# Copy_of_tsop_mux.net
KiCad netlist of a schematic drawn in Altium Designer
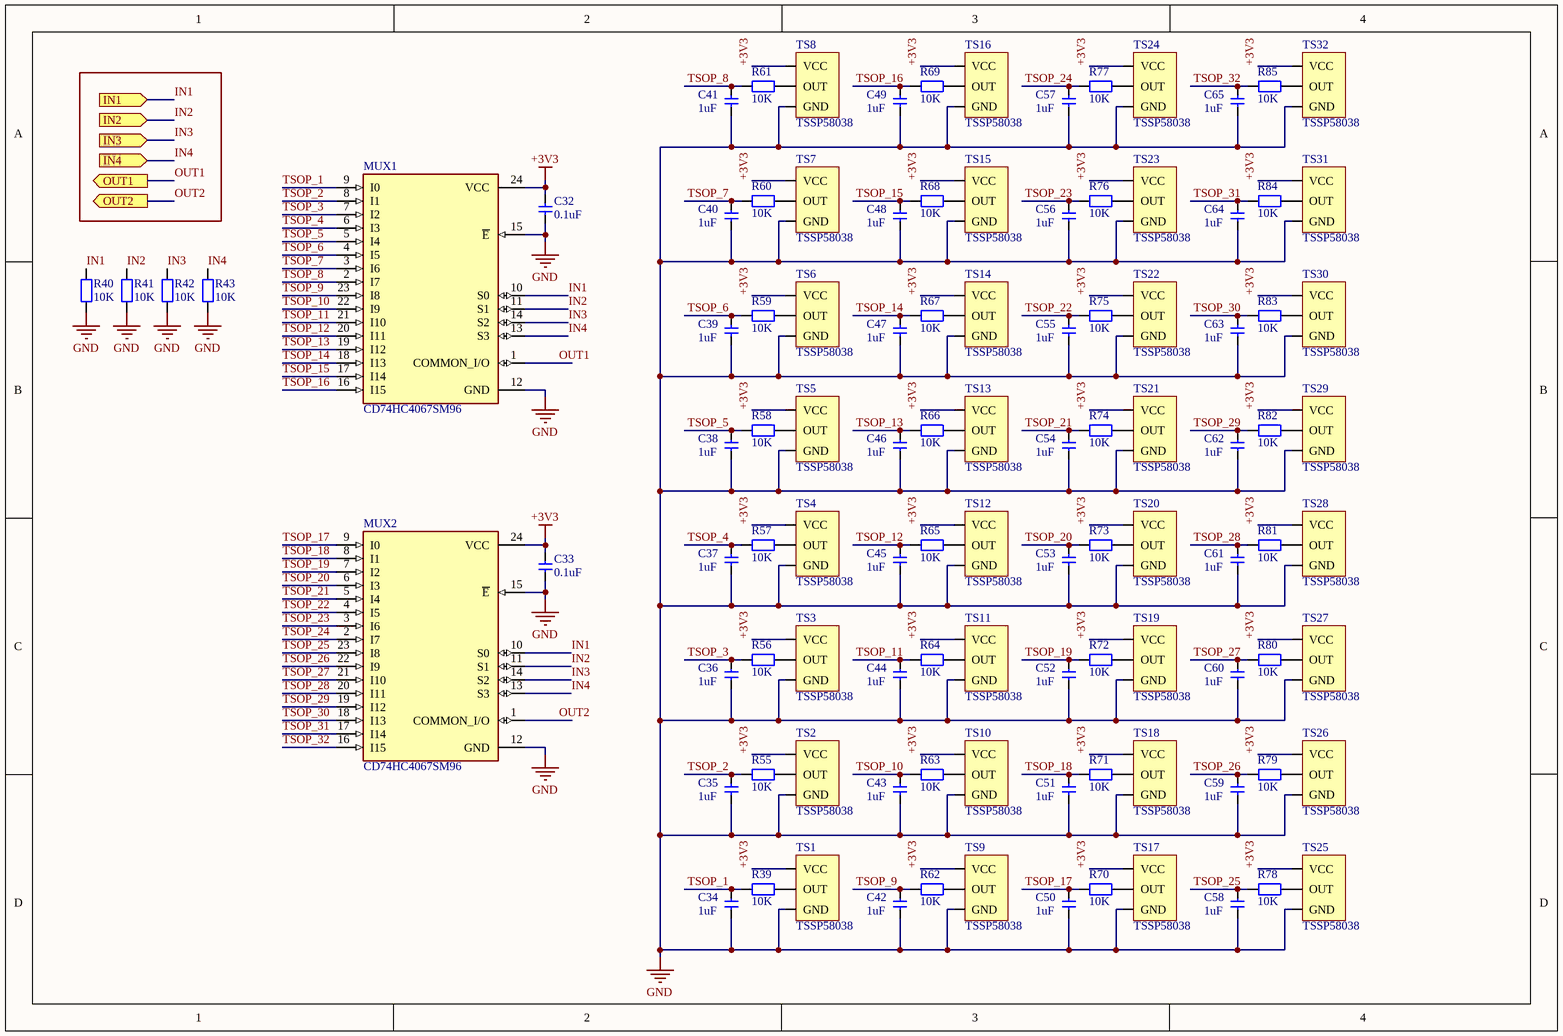
[diagram p0: Copy of tsop_mux.SchDoc]

(export (version "E")
  (design (tool "Eeschema 10.0.6"))
  (components
    (comp (ref "C32")
      (value "0.1uF")
      (footprint "CAP0805")
      (description "Ceramic SMD Cap")
      (libsource (lib "Asterisk") (part "CAP Ceramic"))
    )
    (comp (ref "C33")
      (value "0.1uF")
      (footprint "CAP0805")
      (description "Ceramic SMD Cap")
      (libsource (lib "Asterisk") (part "CAP Ceramic"))
    )
    (comp (ref "C34")
      (value "1uF")
      (footprint "CAP1206")
      (description "Ceramic SMD Cap")
      (libsource (lib "Asterisk") (part "CAP Ceramic"))
    )
    (comp (ref "C35")
      (value "1uF")
      (footprint "CAP1206")
      (description "Ceramic SMD Cap")
      (libsource (lib "Asterisk") (part "CAP Ceramic"))
    )
    (comp (ref "C36")
      (value "1uF")
      (footprint "CAP1206")
      (description "Ceramic SMD Cap")
      (libsource (lib "Asterisk") (part "CAP Ceramic"))
    )
    (comp (ref "C37")
      (value "1uF")
      (footprint "CAP1206")
      (description "Ceramic SMD Cap")
      (libsource (lib "Asterisk") (part "CAP Ceramic"))
    )
    (comp (ref "C38")
      (value "1uF")
      (footprint "CAP1206")
      (description "Ceramic SMD Cap")
      (libsource (lib "Asterisk") (part "CAP Ceramic"))
    )
    (comp (ref "C39")
      (value "1uF")
      (footprint "CAP1206")
      (description "Ceramic SMD Cap")
      (libsource (lib "Asterisk") (part "CAP Ceramic"))
    )
    (comp (ref "C40")
      (value "1uF")
      (footprint "CAP1206")
      (description "Ceramic SMD Cap")
      (libsource (lib "Asterisk") (part "CAP Ceramic"))
    )
    (comp (ref "C41")
      (value "1uF")
      (footprint "CAP1206")
      (description "Ceramic SMD Cap")
      (libsource (lib "Asterisk") (part "CAP Ceramic"))
    )
    (comp (ref "C42")
      (value "1uF")
      (footprint "CAP1206")
      (description "Ceramic SMD Cap")
      (libsource (lib "Asterisk") (part "CAP Ceramic"))
    )
    (comp (ref "C43")
      (value "1uF")
      (footprint "CAP1206")
      (description "Ceramic SMD Cap")
      (libsource (lib "Asterisk") (part "CAP Ceramic"))
    )
    (comp (ref "C44")
      (value "1uF")
      (footprint "CAP1206")
      (description "Ceramic SMD Cap")
      (libsource (lib "Asterisk") (part "CAP Ceramic"))
    )
    (comp (ref "C45")
      (value "1uF")
      (footprint "CAP1206")
      (description "Ceramic SMD Cap")
      (libsource (lib "Asterisk") (part "CAP Ceramic"))
    )
    (comp (ref "C46")
      (value "1uF")
      (footprint "CAP1206")
      (description "Ceramic SMD Cap")
      (libsource (lib "Asterisk") (part "CAP Ceramic"))
    )
    (comp (ref "C47")
      (value "1uF")
      (footprint "CAP1206")
      (description "Ceramic SMD Cap")
      (libsource (lib "Asterisk") (part "CAP Ceramic"))
    )
    (comp (ref "C48")
      (value "1uF")
      (footprint "CAP1206")
      (description "Ceramic SMD Cap")
      (libsource (lib "Asterisk") (part "CAP Ceramic"))
    )
    (comp (ref "C49")
      (value "1uF")
      (footprint "CAP1206")
      (description "Ceramic SMD Cap")
      (libsource (lib "Asterisk") (part "CAP Ceramic"))
    )
    (comp (ref "C50")
      (value "1uF")
      (footprint "CAP1206")
      (description "Ceramic SMD Cap")
      (libsource (lib "Asterisk") (part "CAP Ceramic"))
    )
    (comp (ref "C51")
      (value "1uF")
      (footprint "CAP1206")
      (description "Ceramic SMD Cap")
      (libsource (lib "Asterisk") (part "CAP Ceramic"))
    )
    (comp (ref "C52")
      (value "1uF")
      (footprint "CAP1206")
      (description "Ceramic SMD Cap")
      (libsource (lib "Asterisk") (part "CAP Ceramic"))
    )
    (comp (ref "C53")
      (value "1uF")
      (footprint "CAP1206")
      (description "Ceramic SMD Cap")
      (libsource (lib "Asterisk") (part "CAP Ceramic"))
    )
    (comp (ref "C54")
      (value "1uF")
      (footprint "CAP1206")
      (description "Ceramic SMD Cap")
      (libsource (lib "Asterisk") (part "CAP Ceramic"))
    )
    (comp (ref "C55")
      (value "1uF")
      (footprint "CAP1206")
      (description "Ceramic SMD Cap")
      (libsource (lib "Asterisk") (part "CAP Ceramic"))
    )
    (comp (ref "C56")
      (value "1uF")
      (footprint "CAP1206")
      (description "Ceramic SMD Cap")
      (libsource (lib "Asterisk") (part "CAP Ceramic"))
    )
    (comp (ref "C57")
      (value "1uF")
      (footprint "CAP1206")
      (description "Ceramic SMD Cap")
      (libsource (lib "Asterisk") (part "CAP Ceramic"))
    )
    (comp (ref "C58")
      (value "1uF")
      (footprint "CAP1206")
      (description "Ceramic SMD Cap")
      (libsource (lib "Asterisk") (part "CAP Ceramic"))
    )
    (comp (ref "C59")
      (value "1uF")
      (footprint "CAP1206")
      (description "Ceramic SMD Cap")
      (libsource (lib "Asterisk") (part "CAP Ceramic"))
    )
    (comp (ref "C60")
      (value "1uF")
      (footprint "CAP1206")
      (description "Ceramic SMD Cap")
      (libsource (lib "Asterisk") (part "CAP Ceramic"))
    )
    (comp (ref "C61")
      (value "1uF")
      (footprint "CAP1206")
      (description "Ceramic SMD Cap")
      (libsource (lib "Asterisk") (part "CAP Ceramic"))
    )
    (comp (ref "C62")
      (value "1uF")
      (footprint "CAP1206")
      (description "Ceramic SMD Cap")
      (libsource (lib "Asterisk") (part "CAP Ceramic"))
    )
    (comp (ref "C63")
      (value "1uF")
      (footprint "CAP1206")
      (description "Ceramic SMD Cap")
      (libsource (lib "Asterisk") (part "CAP Ceramic"))
    )
    (comp (ref "C64")
      (value "1uF")
      (footprint "CAP1206")
      (description "Ceramic SMD Cap")
      (libsource (lib "Asterisk") (part "CAP Ceramic"))
    )
    (comp (ref "C65")
      (value "1uF")
      (footprint "CAP1206")
      (description "Ceramic SMD Cap")
      (libsource (lib "Asterisk") (part "CAP Ceramic"))
    )
    (comp (ref "MUX1")
      (value "CD74HC4067SM96")
      (footprint "CD74HC4067SM96")
      (description "SSOP-24")
      (libsource (lib "Asterisk") (part "CD74HC4067SM96"))
    )
    (comp (ref "MUX2")
      (value "CD74HC4067SM96")
      (footprint "CD74HC4067SM96")
      (description "SSOP-24")
      (libsource (lib "Asterisk") (part "CD74HC4067SM96"))
    )
    (comp (ref "R39")
      (value "10K")
      (footprint "RES0603")
      (description "RES smd")
      (libsource (lib "Asterisk") (part "RES"))
    )
    (comp (ref "R40")
      (value "10K")
      (footprint "RES0805")
      (description "RES smd")
      (libsource (lib "Asterisk") (part "RES"))
    )
    (comp (ref "R41")
      (value "10K")
      (footprint "RES0805")
      (description "RES smd")
      (libsource (lib "Asterisk") (part "RES"))
    )
    (comp (ref "R42")
      (value "10K")
      (footprint "RES0805")
      (description "RES smd")
      (libsource (lib "Asterisk") (part "RES"))
    )
    (comp (ref "R43")
      (value "10K")
      (footprint "RES0805")
      (description "RES smd")
      (libsource (lib "Asterisk") (part "RES"))
    )
    (comp (ref "R55")
      (value "10K")
      (footprint "RES0603")
      (description "RES smd")
      (libsource (lib "Asterisk") (part "RES"))
    )
    (comp (ref "R56")
      (value "10K")
      (footprint "RES0603")
      (description "RES smd")
      (libsource (lib "Asterisk") (part "RES"))
    )
    (comp (ref "R57")
      (value "10K")
      (footprint "RES0603")
      (description "RES smd")
      (libsource (lib "Asterisk") (part "RES"))
    )
    (comp (ref "R58")
      (value "10K")
      (footprint "RES0603")
      (description "RES smd")
      (libsource (lib "Asterisk") (part "RES"))
    )
    (comp (ref "R59")
      (value "10K")
      (footprint "RES0603")
      (description "RES smd")
      (libsource (lib "Asterisk") (part "RES"))
    )
    (comp (ref "R60")
      (value "10K")
      (footprint "RES0603")
      (description "RES smd")
      (libsource (lib "Asterisk") (part "RES"))
    )
    (comp (ref "R61")
      (value "10K")
      (footprint "RES0603")
      (description "RES smd")
      (libsource (lib "Asterisk") (part "RES"))
    )
    (comp (ref "R62")
      (value "10K")
      (footprint "RES0603")
      (description "RES smd")
      (libsource (lib "Asterisk") (part "RES"))
    )
    (comp (ref "R63")
      (value "10K")
      (footprint "RES0603")
      (description "RES smd")
      (libsource (lib "Asterisk") (part "RES"))
    )
    (comp (ref "R64")
      (value "10K")
      (footprint "RES0603")
      (description "RES smd")
      (libsource (lib "Asterisk") (part "RES"))
    )
    (comp (ref "R65")
      (value "10K")
      (footprint "RES0603")
      (description "RES smd")
      (libsource (lib "Asterisk") (part "RES"))
    )
    (comp (ref "R66")
      (value "10K")
      (footprint "RES0603")
      (description "RES smd")
      (libsource (lib "Asterisk") (part "RES"))
    )
    (comp (ref "R67")
      (value "10K")
      (footprint "RES0603")
      (description "RES smd")
      (libsource (lib "Asterisk") (part "RES"))
    )
    (comp (ref "R68")
      (value "10K")
      (footprint "RES0603")
      (description "RES smd")
      (libsource (lib "Asterisk") (part "RES"))
    )
    (comp (ref "R69")
      (value "10K")
      (footprint "RES0603")
      (description "RES smd")
      (libsource (lib "Asterisk") (part "RES"))
    )
    (comp (ref "R70")
      (value "10K")
      (footprint "RES0603")
      (description "RES smd")
      (libsource (lib "Asterisk") (part "RES"))
    )
    (comp (ref "R71")
      (value "10K")
      (footprint "RES0603")
      (description "RES smd")
      (libsource (lib "Asterisk") (part "RES"))
    )
    (comp (ref "R72")
      (value "10K")
      (footprint "RES0603")
      (description "RES smd")
      (libsource (lib "Asterisk") (part "RES"))
    )
    (comp (ref "R73")
      (value "10K")
      (footprint "RES0603")
      (description "RES smd")
      (libsource (lib "Asterisk") (part "RES"))
    )
    (comp (ref "R74")
      (value "10K")
      (footprint "RES0603")
      (description "RES smd")
      (libsource (lib "Asterisk") (part "RES"))
    )
    (comp (ref "R75")
      (value "10K")
      (footprint "RES0603")
      (description "RES smd")
      (libsource (lib "Asterisk") (part "RES"))
    )
    (comp (ref "R76")
      (value "10K")
      (footprint "RES0603")
      (description "RES smd")
      (libsource (lib "Asterisk") (part "RES"))
    )
    (comp (ref "R77")
      (value "10K")
      (footprint "RES0603")
      (description "RES smd")
      (libsource (lib "Asterisk") (part "RES"))
    )
    (comp (ref "R78")
      (value "10K")
      (footprint "RES0603")
      (description "RES smd")
      (libsource (lib "Asterisk") (part "RES"))
    )
    (comp (ref "R79")
      (value "10K")
      (footprint "RES0603")
      (description "RES smd")
      (libsource (lib "Asterisk") (part "RES"))
    )
    (comp (ref "R80")
      (value "10K")
      (footprint "RES0603")
      (description "RES smd")
      (libsource (lib "Asterisk") (part "RES"))
    )
    (comp (ref "R81")
      (value "10K")
      (footprint "RES0603")
      (description "RES smd")
      (libsource (lib "Asterisk") (part "RES"))
    )
    (comp (ref "R82")
      (value "10K")
      (footprint "RES0603")
      (description "RES smd")
      (libsource (lib "Asterisk") (part "RES"))
    )
    (comp (ref "R83")
      (value "10K")
      (footprint "RES0603")
      (description "RES smd")
      (libsource (lib "Asterisk") (part "RES"))
    )
    (comp (ref "R84")
      (value "10K")
      (footprint "RES0603")
      (description "RES smd")
      (libsource (lib "Asterisk") (part "RES"))
    )
    (comp (ref "R85")
      (value "10K")
      (footprint "RES0603")
      (description "RES smd")
      (libsource (lib "Asterisk") (part "RES"))
    )
    (comp (ref "TS1")
      (value "TSSP58038")
      (footprint "TSSP58038")
      (libsource (lib "Asterisk") (part "TSSP58038"))
    )
    (comp (ref "TS2")
      (value "TSSP58038")
      (footprint "TSSP58038")
      (libsource (lib "Asterisk") (part "TSSP58038"))
    )
    (comp (ref "TS3")
      (value "TSSP58038")
      (footprint "TSSP58038")
      (libsource (lib "Asterisk") (part "TSSP58038"))
    )
    (comp (ref "TS4")
      (value "TSSP58038")
      (footprint "TSSP58038")
      (libsource (lib "Asterisk") (part "TSSP58038"))
    )
    (comp (ref "TS5")
      (value "TSSP58038")
      (footprint "TSSP58038")
      (libsource (lib "Asterisk") (part "TSSP58038"))
    )
    (comp (ref "TS6")
      (value "TSSP58038")
      (footprint "TSSP58038")
      (libsource (lib "Asterisk") (part "TSSP58038"))
    )
    (comp (ref "TS7")
      (value "TSSP58038")
      (footprint "TSSP58038")
      (libsource (lib "Asterisk") (part "TSSP58038"))
    )
    (comp (ref "TS8")
      (value "TSSP58038")
      (footprint "TSSP58038")
      (libsource (lib "Asterisk") (part "TSSP58038"))
    )
    (comp (ref "TS9")
      (value "TSSP58038")
      (footprint "TSSP58038")
      (libsource (lib "Asterisk") (part "TSSP58038"))
    )
    (comp (ref "TS10")
      (value "TSSP58038")
      (footprint "TSSP58038")
      (libsource (lib "Asterisk") (part "TSSP58038"))
    )
    (comp (ref "TS11")
      (value "TSSP58038")
      (footprint "TSSP58038")
      (libsource (lib "Asterisk") (part "TSSP58038"))
    )
    (comp (ref "TS12")
      (value "TSSP58038")
      (footprint "TSSP58038")
      (libsource (lib "Asterisk") (part "TSSP58038"))
    )
    (comp (ref "TS13")
      (value "TSSP58038")
      (footprint "TSSP58038")
      (libsource (lib "Asterisk") (part "TSSP58038"))
    )
    (comp (ref "TS14")
      (value "TSSP58038")
      (footprint "TSSP58038")
      (libsource (lib "Asterisk") (part "TSSP58038"))
    )
    (comp (ref "TS15")
      (value "TSSP58038")
      (footprint "TSSP58038")
      (libsource (lib "Asterisk") (part "TSSP58038"))
    )
    (comp (ref "TS16")
      (value "TSSP58038")
      (footprint "TSSP58038")
      (libsource (lib "Asterisk") (part "TSSP58038"))
    )
    (comp (ref "TS17")
      (value "TSSP58038")
      (footprint "TSSP58038")
      (libsource (lib "Asterisk") (part "TSSP58038"))
    )
    (comp (ref "TS18")
      (value "TSSP58038")
      (footprint "TSSP58038")
      (libsource (lib "Asterisk") (part "TSSP58038"))
    )
    (comp (ref "TS19")
      (value "TSSP58038")
      (footprint "TSSP58038")
      (libsource (lib "Asterisk") (part "TSSP58038"))
    )
    (comp (ref "TS20")
      (value "TSSP58038")
      (footprint "TSSP58038")
      (libsource (lib "Asterisk") (part "TSSP58038"))
    )
    (comp (ref "TS21")
      (value "TSSP58038")
      (footprint "TSSP58038")
      (libsource (lib "Asterisk") (part "TSSP58038"))
    )
    (comp (ref "TS22")
      (value "TSSP58038")
      (footprint "TSSP58038")
      (libsource (lib "Asterisk") (part "TSSP58038"))
    )
    (comp (ref "TS23")
      (value "TSSP58038")
      (footprint "TSSP58038")
      (libsource (lib "Asterisk") (part "TSSP58038"))
    )
    (comp (ref "TS24")
      (value "TSSP58038")
      (footprint "TSSP58038")
      (libsource (lib "Asterisk") (part "TSSP58038"))
    )
    (comp (ref "TS25")
      (value "TSSP58038")
      (footprint "TSSP58038")
      (libsource (lib "Asterisk") (part "TSSP58038"))
    )
    (comp (ref "TS26")
      (value "TSSP58038")
      (footprint "TSSP58038")
      (libsource (lib "Asterisk") (part "TSSP58038"))
    )
    (comp (ref "TS27")
      (value "TSSP58038")
      (footprint "TSSP58038")
      (libsource (lib "Asterisk") (part "TSSP58038"))
    )
    (comp (ref "TS28")
      (value "TSSP58038")
      (footprint "TSSP58038")
      (libsource (lib "Asterisk") (part "TSSP58038"))
    )
    (comp (ref "TS29")
      (value "TSSP58038")
      (footprint "TSSP58038")
      (libsource (lib "Asterisk") (part "TSSP58038"))
    )
    (comp (ref "TS30")
      (value "TSSP58038")
      (footprint "TSSP58038")
      (libsource (lib "Asterisk") (part "TSSP58038"))
    )
    (comp (ref "TS31")
      (value "TSSP58038")
      (footprint "TSSP58038")
      (libsource (lib "Asterisk") (part "TSSP58038"))
    )
    (comp (ref "TS32")
      (value "TSSP58038")
      (footprint "TSSP58038")
      (libsource (lib "Asterisk") (part "TSSP58038"))
    )
  )
  (nets
    (net (code "1") (name "+3V3") (class "Default")
      (node (ref "C32") (pin "2") (pinfunction "2_2") (pintype "passive"))
      (node (ref "C33") (pin "2") (pinfunction "2_2") (pintype "passive"))
      (node (ref "MUX1") (pin "24") (pinfunction "VCC_24") (pintype "power_in"))
      (node (ref "MUX2") (pin "24") (pinfunction "VCC_24") (pintype "power_in"))
      (node (ref "TS1") (pin "1") (pinfunction "VCC_1") (pintype "passive"))
      (node (ref "TS10") (pin "1") (pinfunction "VCC_1") (pintype "passive"))
      (node (ref "TS11") (pin "1") (pinfunction "VCC_1") (pintype "passive"))
      (node (ref "TS12") (pin "1") (pinfunction "VCC_1") (pintype "passive"))
      (node (ref "TS13") (pin "1") (pinfunction "VCC_1") (pintype "passive"))
      (node (ref "TS14") (pin "1") (pinfunction "VCC_1") (pintype "passive"))
      (node (ref "TS15") (pin "1") (pinfunction "VCC_1") (pintype "passive"))
      (node (ref "TS16") (pin "1") (pinfunction "VCC_1") (pintype "passive"))
      (node (ref "TS17") (pin "1") (pinfunction "VCC_1") (pintype "passive"))
      (node (ref "TS18") (pin "1") (pinfunction "VCC_1") (pintype "passive"))
      (node (ref "TS19") (pin "1") (pinfunction "VCC_1") (pintype "passive"))
      (node (ref "TS2") (pin "1") (pinfunction "VCC_1") (pintype "passive"))
      (node (ref "TS20") (pin "1") (pinfunction "VCC_1") (pintype "passive"))
      (node (ref "TS21") (pin "1") (pinfunction "VCC_1") (pintype "passive"))
      (node (ref "TS22") (pin "1") (pinfunction "VCC_1") (pintype "passive"))
      (node (ref "TS23") (pin "1") (pinfunction "VCC_1") (pintype "passive"))
      (node (ref "TS24") (pin "1") (pinfunction "VCC_1") (pintype "passive"))
      (node (ref "TS25") (pin "1") (pinfunction "VCC_1") (pintype "passive"))
      (node (ref "TS26") (pin "1") (pinfunction "VCC_1") (pintype "passive"))
      (node (ref "TS27") (pin "1") (pinfunction "VCC_1") (pintype "passive"))
      (node (ref "TS28") (pin "1") (pinfunction "VCC_1") (pintype "passive"))
      (node (ref "TS29") (pin "1") (pinfunction "VCC_1") (pintype "passive"))
      (node (ref "TS3") (pin "1") (pinfunction "VCC_1") (pintype "passive"))
      (node (ref "TS30") (pin "1") (pinfunction "VCC_1") (pintype "passive"))
      (node (ref "TS31") (pin "1") (pinfunction "VCC_1") (pintype "passive"))
      (node (ref "TS32") (pin "1") (pinfunction "VCC_1") (pintype "passive"))
      (node (ref "TS4") (pin "1") (pinfunction "VCC_1") (pintype "passive"))
      (node (ref "TS5") (pin "1") (pinfunction "VCC_1") (pintype "passive"))
      (node (ref "TS6") (pin "1") (pinfunction "VCC_1") (pintype "passive"))
      (node (ref "TS7") (pin "1") (pinfunction "VCC_1") (pintype "passive"))
      (node (ref "TS8") (pin "1") (pinfunction "VCC_1") (pintype "passive"))
      (node (ref "TS9") (pin "1") (pinfunction "VCC_1") (pintype "passive"))
    )
    (net (code "2") (name "/IN1") (class "Default")
      (node (ref "MUX1") (pin "10") (pinfunction "S0_10") (pintype "bidirectional"))
      (node (ref "MUX2") (pin "10") (pinfunction "S0_10") (pintype "bidirectional"))
      (node (ref "R40") (pin "2") (pinfunction "2_2") (pintype "passive"))
    )
    (net (code "3") (name "/IN2") (class "Default")
      (node (ref "MUX1") (pin "11") (pinfunction "S1_11") (pintype "bidirectional"))
      (node (ref "MUX2") (pin "11") (pinfunction "S1_11") (pintype "bidirectional"))
      (node (ref "R41") (pin "2") (pinfunction "2_2") (pintype "passive"))
    )
    (net (code "4") (name "/IN3") (class "Default")
      (node (ref "MUX1") (pin "14") (pinfunction "S2_14") (pintype "bidirectional"))
      (node (ref "MUX2") (pin "14") (pinfunction "S2_14") (pintype "bidirectional"))
      (node (ref "R42") (pin "2") (pinfunction "2_2") (pintype "passive"))
    )
    (net (code "5") (name "/IN4") (class "Default")
      (node (ref "MUX1") (pin "13") (pinfunction "S3_13") (pintype "bidirectional"))
      (node (ref "MUX2") (pin "13") (pinfunction "S3_13") (pintype "bidirectional"))
      (node (ref "R43") (pin "2") (pinfunction "2_2") (pintype "passive"))
    )
    (net (code "6") (name "/OUT1") (class "Default")
      (node (ref "MUX1") (pin "1") (pinfunction "COMMON_I/O_1") (pintype "bidirectional"))
    )
    (net (code "7") (name "/OUT2") (class "Default")
      (node (ref "MUX2") (pin "1") (pinfunction "COMMON_I/O_1") (pintype "bidirectional"))
    )
    (net (code "8") (name "/TSOP_1") (class "Default")
      (node (ref "C34") (pin "1") (pinfunction "1_1") (pintype "passive"))
      (node (ref "MUX1") (pin "9") (pinfunction "I0_9") (pintype "input"))
      (node (ref "R39") (pin "1") (pinfunction "1_1") (pintype "passive"))
    )
    (net (code "9") (name "/TSOP_2") (class "Default")
      (node (ref "C35") (pin "1") (pinfunction "1_1") (pintype "passive"))
      (node (ref "MUX1") (pin "8") (pinfunction "I1_8") (pintype "input"))
      (node (ref "R55") (pin "1") (pinfunction "1_1") (pintype "passive"))
    )
    (net (code "10") (name "/TSOP_3") (class "Default")
      (node (ref "C36") (pin "1") (pinfunction "1_1") (pintype "passive"))
      (node (ref "MUX1") (pin "7") (pinfunction "I2_7") (pintype "input"))
      (node (ref "R56") (pin "1") (pinfunction "1_1") (pintype "passive"))
    )
    (net (code "11") (name "/TSOP_4") (class "Default")
      (node (ref "C37") (pin "1") (pinfunction "1_1") (pintype "passive"))
      (node (ref "MUX1") (pin "6") (pinfunction "I3_6") (pintype "input"))
      (node (ref "R57") (pin "1") (pinfunction "1_1") (pintype "passive"))
    )
    (net (code "12") (name "/TSOP_5") (class "Default")
      (node (ref "C38") (pin "1") (pinfunction "1_1") (pintype "passive"))
      (node (ref "MUX1") (pin "5") (pinfunction "I4_5") (pintype "input"))
      (node (ref "R58") (pin "1") (pinfunction "1_1") (pintype "passive"))
    )
    (net (code "13") (name "/TSOP_6") (class "Default")
      (node (ref "C39") (pin "1") (pinfunction "1_1") (pintype "passive"))
      (node (ref "MUX1") (pin "4") (pinfunction "I5_4") (pintype "input"))
      (node (ref "R59") (pin "1") (pinfunction "1_1") (pintype "passive"))
    )
    (net (code "14") (name "/TSOP_7") (class "Default")
      (node (ref "C40") (pin "1") (pinfunction "1_1") (pintype "passive"))
      (node (ref "MUX1") (pin "3") (pinfunction "I6_3") (pintype "input"))
      (node (ref "R60") (pin "1") (pinfunction "1_1") (pintype "passive"))
    )
    (net (code "15") (name "/TSOP_8") (class "Default")
      (node (ref "C41") (pin "1") (pinfunction "1_1") (pintype "passive"))
      (node (ref "MUX1") (pin "2") (pinfunction "I7_2") (pintype "input"))
      (node (ref "R61") (pin "1") (pinfunction "1_1") (pintype "passive"))
    )
    (net (code "16") (name "/TSOP_9") (class "Default")
      (node (ref "C42") (pin "1") (pinfunction "1_1") (pintype "passive"))
      (node (ref "MUX1") (pin "23") (pinfunction "I8_23") (pintype "input"))
      (node (ref "R62") (pin "1") (pinfunction "1_1") (pintype "passive"))
    )
    (net (code "17") (name "/TSOP_10") (class "Default")
      (node (ref "C43") (pin "1") (pinfunction "1_1") (pintype "passive"))
      (node (ref "MUX1") (pin "22") (pinfunction "I9_22") (pintype "input"))
      (node (ref "R63") (pin "1") (pinfunction "1_1") (pintype "passive"))
    )
    (net (code "18") (name "/TSOP_11") (class "Default")
      (node (ref "C44") (pin "1") (pinfunction "1_1") (pintype "passive"))
      (node (ref "MUX1") (pin "21") (pinfunction "I10_21") (pintype "input"))
      (node (ref "R64") (pin "1") (pinfunction "1_1") (pintype "passive"))
    )
    (net (code "19") (name "/TSOP_12") (class "Default")
      (node (ref "C45") (pin "1") (pinfunction "1_1") (pintype "passive"))
      (node (ref "MUX1") (pin "20") (pinfunction "I11_20") (pintype "input"))
      (node (ref "R65") (pin "1") (pinfunction "1_1") (pintype "passive"))
    )
    (net (code "20") (name "/TSOP_13") (class "Default")
      (node (ref "C46") (pin "1") (pinfunction "1_1") (pintype "passive"))
      (node (ref "MUX1") (pin "19") (pinfunction "I12_19") (pintype "input"))
      (node (ref "R66") (pin "1") (pinfunction "1_1") (pintype "passive"))
    )
    (net (code "21") (name "/TSOP_14") (class "Default")
      (node (ref "C47") (pin "1") (pinfunction "1_1") (pintype "passive"))
      (node (ref "MUX1") (pin "18") (pinfunction "I13_18") (pintype "input"))
      (node (ref "R67") (pin "1") (pinfunction "1_1") (pintype "passive"))
    )
    (net (code "22") (name "/TSOP_15") (class "Default")
      (node (ref "C48") (pin "1") (pinfunction "1_1") (pintype "passive"))
      (node (ref "MUX1") (pin "17") (pinfunction "I14_17") (pintype "input"))
      (node (ref "R68") (pin "1") (pinfunction "1_1") (pintype "passive"))
    )
    (net (code "23") (name "/TSOP_16") (class "Default")
      (node (ref "C49") (pin "1") (pinfunction "1_1") (pintype "passive"))
      (node (ref "MUX1") (pin "16") (pinfunction "I15_16") (pintype "input"))
      (node (ref "R69") (pin "1") (pinfunction "1_1") (pintype "passive"))
    )
    (net (code "24") (name "/TSOP_17") (class "Default")
      (node (ref "C50") (pin "1") (pinfunction "1_1") (pintype "passive"))
      (node (ref "MUX2") (pin "9") (pinfunction "I0_9") (pintype "input"))
      (node (ref "R70") (pin "1") (pinfunction "1_1") (pintype "passive"))
    )
    (net (code "25") (name "/TSOP_18") (class "Default")
      (node (ref "C51") (pin "1") (pinfunction "1_1") (pintype "passive"))
      (node (ref "MUX2") (pin "8") (pinfunction "I1_8") (pintype "input"))
      (node (ref "R71") (pin "1") (pinfunction "1_1") (pintype "passive"))
    )
    (net (code "26") (name "/TSOP_19") (class "Default")
      (node (ref "C52") (pin "1") (pinfunction "1_1") (pintype "passive"))
      (node (ref "MUX2") (pin "7") (pinfunction "I2_7") (pintype "input"))
      (node (ref "R72") (pin "1") (pinfunction "1_1") (pintype "passive"))
    )
    (net (code "27") (name "/TSOP_20") (class "Default")
      (node (ref "C53") (pin "1") (pinfunction "1_1") (pintype "passive"))
      (node (ref "MUX2") (pin "6") (pinfunction "I3_6") (pintype "input"))
      (node (ref "R73") (pin "1") (pinfunction "1_1") (pintype "passive"))
    )
    (net (code "28") (name "/TSOP_21") (class "Default")
      (node (ref "C54") (pin "1") (pinfunction "1_1") (pintype "passive"))
      (node (ref "MUX2") (pin "5") (pinfunction "I4_5") (pintype "input"))
      (node (ref "R74") (pin "1") (pinfunction "1_1") (pintype "passive"))
    )
    (net (code "29") (name "/TSOP_22") (class "Default")
      (node (ref "C55") (pin "1") (pinfunction "1_1") (pintype "passive"))
      (node (ref "MUX2") (pin "4") (pinfunction "I5_4") (pintype "input"))
      (node (ref "R75") (pin "1") (pinfunction "1_1") (pintype "passive"))
    )
    (net (code "30") (name "/TSOP_23") (class "Default")
      (node (ref "C56") (pin "1") (pinfunction "1_1") (pintype "passive"))
      (node (ref "MUX2") (pin "3") (pinfunction "I6_3") (pintype "input"))
      (node (ref "R76") (pin "1") (pinfunction "1_1") (pintype "passive"))
    )
    (net (code "31") (name "/TSOP_24") (class "Default")
      (node (ref "C57") (pin "1") (pinfunction "1_1") (pintype "passive"))
      (node (ref "MUX2") (pin "2") (pinfunction "I7_2") (pintype "input"))
      (node (ref "R77") (pin "1") (pinfunction "1_1") (pintype "passive"))
    )
    (net (code "32") (name "/TSOP_25") (class "Default")
      (node (ref "C58") (pin "1") (pinfunction "1_1") (pintype "passive"))
      (node (ref "MUX2") (pin "23") (pinfunction "I8_23") (pintype "input"))
      (node (ref "R78") (pin "1") (pinfunction "1_1") (pintype "passive"))
    )
    (net (code "33") (name "/TSOP_26") (class "Default")
      (node (ref "C59") (pin "1") (pinfunction "1_1") (pintype "passive"))
      (node (ref "MUX2") (pin "22") (pinfunction "I9_22") (pintype "input"))
      (node (ref "R79") (pin "1") (pinfunction "1_1") (pintype "passive"))
    )
    (net (code "34") (name "/TSOP_27") (class "Default")
      (node (ref "C60") (pin "1") (pinfunction "1_1") (pintype "passive"))
      (node (ref "MUX2") (pin "21") (pinfunction "I10_21") (pintype "input"))
      (node (ref "R80") (pin "1") (pinfunction "1_1") (pintype "passive"))
    )
    (net (code "35") (name "/TSOP_28") (class "Default")
      (node (ref "C61") (pin "1") (pinfunction "1_1") (pintype "passive"))
      (node (ref "MUX2") (pin "20") (pinfunction "I11_20") (pintype "input"))
      (node (ref "R81") (pin "1") (pinfunction "1_1") (pintype "passive"))
    )
    (net (code "36") (name "/TSOP_29") (class "Default")
      (node (ref "C62") (pin "1") (pinfunction "1_1") (pintype "passive"))
      (node (ref "MUX2") (pin "19") (pinfunction "I12_19") (pintype "input"))
      (node (ref "R82") (pin "1") (pinfunction "1_1") (pintype "passive"))
    )
    (net (code "37") (name "/TSOP_30") (class "Default")
      (node (ref "C63") (pin "1") (pinfunction "1_1") (pintype "passive"))
      (node (ref "MUX2") (pin "18") (pinfunction "I13_18") (pintype "input"))
      (node (ref "R83") (pin "1") (pinfunction "1_1") (pintype "passive"))
    )
    (net (code "38") (name "/TSOP_31") (class "Default")
      (node (ref "C64") (pin "1") (pinfunction "1_1") (pintype "passive"))
      (node (ref "MUX2") (pin "17") (pinfunction "I14_17") (pintype "input"))
      (node (ref "R84") (pin "1") (pinfunction "1_1") (pintype "passive"))
    )
    (net (code "39") (name "/TSOP_32") (class "Default")
      (node (ref "C65") (pin "1") (pinfunction "1_1") (pintype "passive"))
      (node (ref "MUX2") (pin "16") (pinfunction "I15_16") (pintype "input"))
      (node (ref "R85") (pin "1") (pinfunction "1_1") (pintype "passive"))
    )
    (net (code "40") (name "GND") (class "Default")
      (node (ref "C32") (pin "1") (pinfunction "1_1") (pintype "passive"))
      (node (ref "C33") (pin "1") (pinfunction "1_1") (pintype "passive"))
      (node (ref "C34") (pin "2") (pinfunction "2_2") (pintype "passive"))
      (node (ref "C35") (pin "2") (pinfunction "2_2") (pintype "passive"))
      (node (ref "C36") (pin "2") (pinfunction "2_2") (pintype "passive"))
      (node (ref "C37") (pin "2") (pinfunction "2_2") (pintype "passive"))
      (node (ref "C38") (pin "2") (pinfunction "2_2") (pintype "passive"))
      (node (ref "C39") (pin "2") (pinfunction "2_2") (pintype "passive"))
      (node (ref "C40") (pin "2") (pinfunction "2_2") (pintype "passive"))
      (node (ref "C41") (pin "2") (pinfunction "2_2") (pintype "passive"))
      (node (ref "C42") (pin "2") (pinfunction "2_2") (pintype "passive"))
      (node (ref "C43") (pin "2") (pinfunction "2_2") (pintype "passive"))
      (node (ref "C44") (pin "2") (pinfunction "2_2") (pintype "passive"))
      (node (ref "C45") (pin "2") (pinfunction "2_2") (pintype "passive"))
      (node (ref "C46") (pin "2") (pinfunction "2_2") (pintype "passive"))
      (node (ref "C47") (pin "2") (pinfunction "2_2") (pintype "passive"))
      (node (ref "C48") (pin "2") (pinfunction "2_2") (pintype "passive"))
      (node (ref "C49") (pin "2") (pinfunction "2_2") (pintype "passive"))
      (node (ref "C50") (pin "2") (pinfunction "2_2") (pintype "passive"))
      (node (ref "C51") (pin "2") (pinfunction "2_2") (pintype "passive"))
      (node (ref "C52") (pin "2") (pinfunction "2_2") (pintype "passive"))
      (node (ref "C53") (pin "2") (pinfunction "2_2") (pintype "passive"))
      (node (ref "C54") (pin "2") (pinfunction "2_2") (pintype "passive"))
      (node (ref "C55") (pin "2") (pinfunction "2_2") (pintype "passive"))
      (node (ref "C56") (pin "2") (pinfunction "2_2") (pintype "passive"))
      (node (ref "C57") (pin "2") (pinfunction "2_2") (pintype "passive"))
      (node (ref "C58") (pin "2") (pinfunction "2_2") (pintype "passive"))
      (node (ref "C59") (pin "2") (pinfunction "2_2") (pintype "passive"))
      (node (ref "C60") (pin "2") (pinfunction "2_2") (pintype "passive"))
      (node (ref "C61") (pin "2") (pinfunction "2_2") (pintype "passive"))
      (node (ref "C62") (pin "2") (pinfunction "2_2") (pintype "passive"))
      (node (ref "C63") (pin "2") (pinfunction "2_2") (pintype "passive"))
      (node (ref "C64") (pin "2") (pinfunction "2_2") (pintype "passive"))
      (node (ref "C65") (pin "2") (pinfunction "2_2") (pintype "passive"))
      (node (ref "MUX1") (pin "12") (pinfunction "GND_12") (pintype "power_in"))
      (node (ref "MUX1") (pin "15") (pinfunction "~{E}_15") (pintype "input"))
      (node (ref "MUX2") (pin "12") (pinfunction "GND_12") (pintype "power_in"))
      (node (ref "MUX2") (pin "15") (pinfunction "~{E}_15") (pintype "input"))
      (node (ref "R40") (pin "1") (pinfunction "1_1") (pintype "passive"))
      (node (ref "R41") (pin "1") (pinfunction "1_1") (pintype "passive"))
      (node (ref "R42") (pin "1") (pinfunction "1_1") (pintype "passive"))
      (node (ref "R43") (pin "1") (pinfunction "1_1") (pintype "passive"))
      (node (ref "TS1") (pin "2") (pinfunction "GND_2") (pintype "passive"))
      (node (ref "TS10") (pin "2") (pinfunction "GND_2") (pintype "passive"))
      (node (ref "TS11") (pin "2") (pinfunction "GND_2") (pintype "passive"))
      (node (ref "TS12") (pin "2") (pinfunction "GND_2") (pintype "passive"))
      (node (ref "TS13") (pin "2") (pinfunction "GND_2") (pintype "passive"))
      (node (ref "TS14") (pin "2") (pinfunction "GND_2") (pintype "passive"))
      (node (ref "TS15") (pin "2") (pinfunction "GND_2") (pintype "passive"))
      (node (ref "TS16") (pin "2") (pinfunction "GND_2") (pintype "passive"))
      (node (ref "TS17") (pin "2") (pinfunction "GND_2") (pintype "passive"))
      (node (ref "TS18") (pin "2") (pinfunction "GND_2") (pintype "passive"))
      (node (ref "TS19") (pin "2") (pinfunction "GND_2") (pintype "passive"))
      (node (ref "TS2") (pin "2") (pinfunction "GND_2") (pintype "passive"))
      (node (ref "TS20") (pin "2") (pinfunction "GND_2") (pintype "passive"))
      (node (ref "TS21") (pin "2") (pinfunction "GND_2") (pintype "passive"))
      (node (ref "TS22") (pin "2") (pinfunction "GND_2") (pintype "passive"))
      (node (ref "TS23") (pin "2") (pinfunction "GND_2") (pintype "passive"))
      (node (ref "TS24") (pin "2") (pinfunction "GND_2") (pintype "passive"))
      (node (ref "TS25") (pin "2") (pinfunction "GND_2") (pintype "passive"))
      (node (ref "TS26") (pin "2") (pinfunction "GND_2") (pintype "passive"))
      (node (ref "TS27") (pin "2") (pinfunction "GND_2") (pintype "passive"))
      (node (ref "TS28") (pin "2") (pinfunction "GND_2") (pintype "passive"))
      (node (ref "TS29") (pin "2") (pinfunction "GND_2") (pintype "passive"))
      (node (ref "TS3") (pin "2") (pinfunction "GND_2") (pintype "passive"))
      (node (ref "TS30") (pin "2") (pinfunction "GND_2") (pintype "passive"))
      (node (ref "TS31") (pin "2") (pinfunction "GND_2") (pintype "passive"))
      (node (ref "TS32") (pin "2") (pinfunction "GND_2") (pintype "passive"))
      (node (ref "TS4") (pin "2") (pinfunction "GND_2") (pintype "passive"))
      (node (ref "TS5") (pin "2") (pinfunction "GND_2") (pintype "passive"))
      (node (ref "TS6") (pin "2") (pinfunction "GND_2") (pintype "passive"))
      (node (ref "TS7") (pin "2") (pinfunction "GND_2") (pintype "passive"))
      (node (ref "TS8") (pin "2") (pinfunction "GND_2") (pintype "passive"))
      (node (ref "TS9") (pin "2") (pinfunction "GND_2") (pintype "passive"))
    )
    (net (code "41") (name "Net-(TS1-OUT)") (class "Default")
      (node (ref "R39") (pin "2") (pinfunction "2_2") (pintype "passive"))
      (node (ref "TS1") (pin "3") (pinfunction "OUT_3") (pintype "passive"))
    )
    (net (code "42") (name "Net-(TS2-OUT)") (class "Default")
      (node (ref "R55") (pin "2") (pinfunction "2_2") (pintype "passive"))
      (node (ref "TS2") (pin "3") (pinfunction "OUT_3") (pintype "passive"))
    )
    (net (code "43") (name "Net-(TS3-OUT)") (class "Default")
      (node (ref "R56") (pin "2") (pinfunction "2_2") (pintype "passive"))
      (node (ref "TS3") (pin "3") (pinfunction "OUT_3") (pintype "passive"))
    )
    (net (code "44") (name "Net-(TS4-OUT)") (class "Default")
      (node (ref "R57") (pin "2") (pinfunction "2_2") (pintype "passive"))
      (node (ref "TS4") (pin "3") (pinfunction "OUT_3") (pintype "passive"))
    )
    (net (code "45") (name "Net-(TS5-OUT)") (class "Default")
      (node (ref "R58") (pin "2") (pinfunction "2_2") (pintype "passive"))
      (node (ref "TS5") (pin "3") (pinfunction "OUT_3") (pintype "passive"))
    )
    (net (code "46") (name "Net-(TS6-OUT)") (class "Default")
      (node (ref "R59") (pin "2") (pinfunction "2_2") (pintype "passive"))
      (node (ref "TS6") (pin "3") (pinfunction "OUT_3") (pintype "passive"))
    )
    (net (code "47") (name "Net-(TS7-OUT)") (class "Default")
      (node (ref "R60") (pin "2") (pinfunction "2_2") (pintype "passive"))
      (node (ref "TS7") (pin "3") (pinfunction "OUT_3") (pintype "passive"))
    )
    (net (code "48") (name "Net-(TS8-OUT)") (class "Default")
      (node (ref "R61") (pin "2") (pinfunction "2_2") (pintype "passive"))
      (node (ref "TS8") (pin "3") (pinfunction "OUT_3") (pintype "passive"))
    )
    (net (code "49") (name "Net-(TS9-OUT)") (class "Default")
      (node (ref "R62") (pin "2") (pinfunction "2_2") (pintype "passive"))
      (node (ref "TS9") (pin "3") (pinfunction "OUT_3") (pintype "passive"))
    )
    (net (code "50") (name "Net-(TS10-OUT)") (class "Default")
      (node (ref "R63") (pin "2") (pinfunction "2_2") (pintype "passive"))
      (node (ref "TS10") (pin "3") (pinfunction "OUT_3") (pintype "passive"))
    )
    (net (code "51") (name "Net-(TS11-OUT)") (class "Default")
      (node (ref "R64") (pin "2") (pinfunction "2_2") (pintype "passive"))
      (node (ref "TS11") (pin "3") (pinfunction "OUT_3") (pintype "passive"))
    )
    (net (code "52") (name "Net-(TS12-OUT)") (class "Default")
      (node (ref "R65") (pin "2") (pinfunction "2_2") (pintype "passive"))
      (node (ref "TS12") (pin "3") (pinfunction "OUT_3") (pintype "passive"))
    )
    (net (code "53") (name "Net-(TS13-OUT)") (class "Default")
      (node (ref "R66") (pin "2") (pinfunction "2_2") (pintype "passive"))
      (node (ref "TS13") (pin "3") (pinfunction "OUT_3") (pintype "passive"))
    )
    (net (code "54") (name "Net-(TS14-OUT)") (class "Default")
      (node (ref "R67") (pin "2") (pinfunction "2_2") (pintype "passive"))
      (node (ref "TS14") (pin "3") (pinfunction "OUT_3") (pintype "passive"))
    )
    (net (code "55") (name "Net-(TS15-OUT)") (class "Default")
      (node (ref "R68") (pin "2") (pinfunction "2_2") (pintype "passive"))
      (node (ref "TS15") (pin "3") (pinfunction "OUT_3") (pintype "passive"))
    )
    (net (code "56") (name "Net-(TS16-OUT)") (class "Default")
      (node (ref "R69") (pin "2") (pinfunction "2_2") (pintype "passive"))
      (node (ref "TS16") (pin "3") (pinfunction "OUT_3") (pintype "passive"))
    )
    (net (code "57") (name "Net-(TS17-OUT)") (class "Default")
      (node (ref "R70") (pin "2") (pinfunction "2_2") (pintype "passive"))
      (node (ref "TS17") (pin "3") (pinfunction "OUT_3") (pintype "passive"))
    )
    (net (code "58") (name "Net-(TS18-OUT)") (class "Default")
      (node (ref "R71") (pin "2") (pinfunction "2_2") (pintype "passive"))
      (node (ref "TS18") (pin "3") (pinfunction "OUT_3") (pintype "passive"))
    )
    (net (code "59") (name "Net-(TS19-OUT)") (class "Default")
      (node (ref "R72") (pin "2") (pinfunction "2_2") (pintype "passive"))
      (node (ref "TS19") (pin "3") (pinfunction "OUT_3") (pintype "passive"))
    )
    (net (code "60") (name "Net-(TS20-OUT)") (class "Default")
      (node (ref "R73") (pin "2") (pinfunction "2_2") (pintype "passive"))
      (node (ref "TS20") (pin "3") (pinfunction "OUT_3") (pintype "passive"))
    )
    (net (code "61") (name "Net-(TS21-OUT)") (class "Default")
      (node (ref "R74") (pin "2") (pinfunction "2_2") (pintype "passive"))
      (node (ref "TS21") (pin "3") (pinfunction "OUT_3") (pintype "passive"))
    )
    (net (code "62") (name "Net-(TS22-OUT)") (class "Default")
      (node (ref "R75") (pin "2") (pinfunction "2_2") (pintype "passive"))
      (node (ref "TS22") (pin "3") (pinfunction "OUT_3") (pintype "passive"))
    )
    (net (code "63") (name "Net-(TS23-OUT)") (class "Default")
      (node (ref "R76") (pin "2") (pinfunction "2_2") (pintype "passive"))
      (node (ref "TS23") (pin "3") (pinfunction "OUT_3") (pintype "passive"))
    )
    (net (code "64") (name "Net-(TS24-OUT)") (class "Default")
      (node (ref "R77") (pin "2") (pinfunction "2_2") (pintype "passive"))
      (node (ref "TS24") (pin "3") (pinfunction "OUT_3") (pintype "passive"))
    )
    (net (code "65") (name "Net-(TS25-OUT)") (class "Default")
      (node (ref "R78") (pin "2") (pinfunction "2_2") (pintype "passive"))
      (node (ref "TS25") (pin "3") (pinfunction "OUT_3") (pintype "passive"))
    )
    (net (code "66") (name "Net-(TS26-OUT)") (class "Default")
      (node (ref "R79") (pin "2") (pinfunction "2_2") (pintype "passive"))
      (node (ref "TS26") (pin "3") (pinfunction "OUT_3") (pintype "passive"))
    )
    (net (code "67") (name "Net-(TS27-OUT)") (class "Default")
      (node (ref "R80") (pin "2") (pinfunction "2_2") (pintype "passive"))
      (node (ref "TS27") (pin "3") (pinfunction "OUT_3") (pintype "passive"))
    )
    (net (code "68") (name "Net-(TS28-OUT)") (class "Default")
      (node (ref "R81") (pin "2") (pinfunction "2_2") (pintype "passive"))
      (node (ref "TS28") (pin "3") (pinfunction "OUT_3") (pintype "passive"))
    )
    (net (code "69") (name "Net-(TS29-OUT)") (class "Default")
      (node (ref "R82") (pin "2") (pinfunction "2_2") (pintype "passive"))
      (node (ref "TS29") (pin "3") (pinfunction "OUT_3") (pintype "passive"))
    )
    (net (code "70") (name "Net-(TS30-OUT)") (class "Default")
      (node (ref "R83") (pin "2") (pinfunction "2_2") (pintype "passive"))
      (node (ref "TS30") (pin "3") (pinfunction "OUT_3") (pintype "passive"))
    )
    (net (code "71") (name "Net-(TS31-OUT)") (class "Default")
      (node (ref "R84") (pin "2") (pinfunction "2_2") (pintype "passive"))
      (node (ref "TS31") (pin "3") (pinfunction "OUT_3") (pintype "passive"))
    )
    (net (code "72") (name "Net-(TS32-OUT)") (class "Default")
      (node (ref "R85") (pin "2") (pinfunction "2_2") (pintype "passive"))
      (node (ref "TS32") (pin "3") (pinfunction "OUT_3") (pintype "passive"))
    )
  )
)
